# Roberto_shield_sch.net
KiCad netlist of a schematic drawn in Altium Designer
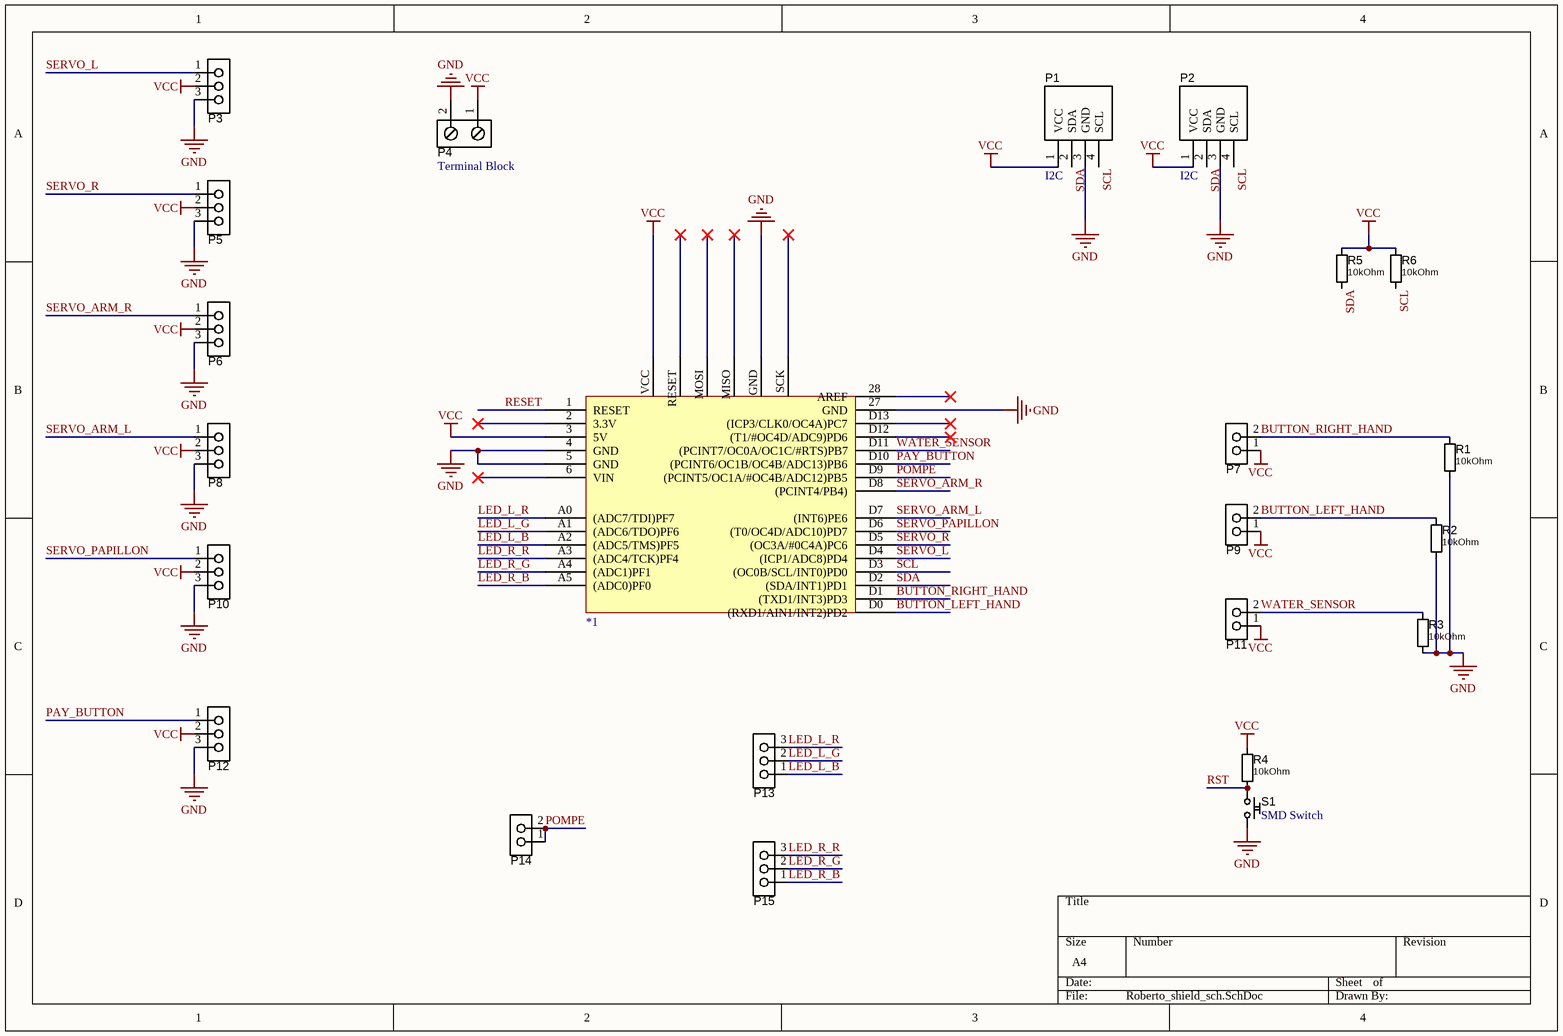
[diagram p0: Roberto_shield_sch.SchDoc]

(export (version "E")
  (design (tool "Eeschema 10.0.6"))
  (components
    (comp (ref "*1")
      (value "Leonardo pins with ISP")
      (footprint "Leonardo pins with ISP")
      (libsource (lib "patricklib") (part "Leonardo pins with ISP"))
    )
    (comp (ref "P1")
      (value "I2C")
      (footprint "TYCO/215079-4")
      (description "Micromatch I2C Connector")
      (libsource (lib "andylib") (part "Micromatch-I2C"))
    )
    (comp (ref "P2")
      (value "I2C")
      (footprint "TYCO/215079-4")
      (description "Micromatch I2C Connector")
      (libsource (lib "andylib") (part "Micromatch-I2C"))
    )
    (comp (ref "P3")
      (value "Header 3")
      (footprint "HEADER1x3")
      (description "Header, 3-Pin")
      (fields (field (name "PUBLISHER") "Altium Limited"))
      (libsource (lib "") (part "Header 3_1"))
    )
    (comp (ref "P4")
      (value "Terminal Block")
      (footprint "Phoenix PT 2-Pole")
      (description "2-Pin Screw Terminal")
      (fields (field (name "PUBLISHER") "Altium Limited"))
      (libsource (lib "andylib") (part "Screw Block 2"))
    )
    (comp (ref "P5")
      (value "Header 3")
      (footprint "HEADER1x3")
      (description "Header, 3-Pin")
      (fields (field (name "PUBLISHER") "Altium Limited"))
      (libsource (lib "") (part "Header 3_1"))
    )
    (comp (ref "P6")
      (value "Header 3")
      (footprint "HEADER1x3")
      (description "Header, 3-Pin")
      (fields (field (name "PUBLISHER") "Altium Limited"))
      (libsource (lib "") (part "Header 3_1"))
    )
    (comp (ref "P7")
      (value "Header 2")
      (footprint "HEADER1x2")
      (description "Header, 2-Pin")
      (fields (field (name "PUBLISHER") "Altium Limited"))
      (libsource (lib "andylib") (part "Header 2"))
    )
    (comp (ref "P8")
      (value "Header 3")
      (footprint "HEADER1x3")
      (description "Header, 3-Pin")
      (fields (field (name "PUBLISHER") "Altium Limited"))
      (libsource (lib "") (part "Header 3_1"))
    )
    (comp (ref "P9")
      (value "Header 2")
      (footprint "HEADER1x2")
      (description "Header, 2-Pin")
      (fields (field (name "PUBLISHER") "Altium Limited"))
      (libsource (lib "andylib") (part "Header 2"))
    )
    (comp (ref "P10")
      (value "Header 3")
      (footprint "HEADER1x3")
      (description "Header, 3-Pin")
      (fields (field (name "PUBLISHER") "Altium Limited"))
      (libsource (lib "") (part "Header 3_1"))
    )
    (comp (ref "P11")
      (value "Header 2")
      (footprint "HEADER1x2")
      (description "Header, 2-Pin")
      (fields (field (name "PUBLISHER") "Altium Limited"))
      (libsource (lib "andylib") (part "Header 2"))
    )
    (comp (ref "P12")
      (value "Header 3")
      (footprint "HEADER1x3")
      (description "Header, 3-Pin")
      (fields (field (name "PUBLISHER") "Altium Limited"))
      (libsource (lib "") (part "Header 3_1"))
    )
    (comp (ref "P13")
      (value "Header 3")
      (footprint "HEADER1x3")
      (description "Header, 3-Pin")
      (fields (field (name "PUBLISHER") "Altium Limited"))
      (libsource (lib "andylib") (part "Header 3"))
    )
    (comp (ref "P14")
      (value "Header 2")
      (footprint "HEADER1x2")
      (description "Header, 2-Pin")
      (fields (field (name "PUBLISHER") "Altium Limited"))
      (libsource (lib "andylib") (part "Header 2"))
    )
    (comp (ref "P15")
      (value "Header 3")
      (footprint "HEADER1x3")
      (description "Header, 3-Pin")
      (fields (field (name "PUBLISHER") "Altium Limited"))
      (libsource (lib "andylib") (part "Header 3"))
    )
    (comp (ref "R1")
      (value "10kOhm")
      (footprint "R/0805")
      (description "Resistor")
      (fields (field (name "PUBLISHER") "Altium Limited"))
      (libsource (lib "andylib") (part "R"))
    )
    (comp (ref "R2")
      (value "10kOhm")
      (footprint "R/0805")
      (description "Resistor")
      (fields (field (name "PUBLISHER") "Altium Limited"))
      (libsource (lib "andylib") (part "R"))
    )
    (comp (ref "R3")
      (value "10kOhm")
      (footprint "R/0805")
      (description "Resistor")
      (fields (field (name "PUBLISHER") "Altium Limited"))
      (libsource (lib "andylib") (part "R"))
    )
    (comp (ref "R4")
      (value "10kOhm")
      (footprint "R/0805")
      (description "Resistor")
      (fields (field (name "PUBLISHER") "Altium Limited"))
      (libsource (lib "andylib") (part "R"))
    )
    (comp (ref "R5")
      (value "10kOhm")
      (footprint "R/0805")
      (description "Resistor")
      (fields (field (name "PUBLISHER") "Altium Limited"))
      (libsource (lib "andylib") (part "R"))
    )
    (comp (ref "R6")
      (value "10kOhm")
      (footprint "R/0805")
      (description "Resistor")
      (fields (field (name "PUBLISHER") "Altium Limited"))
      (libsource (lib "andylib") (part "R"))
    )
    (comp (ref "S1")
      (value "SMD Switch")
      (footprint "SMD_SW_Red")
      (description "Switch")
      (fields (field (name "PUBLISHER") "Altium Limited"))
      (libsource (lib "andylib") (part "SMD Switch"))
    )
  )
  (nets
    (net (code "1") (name "/BUTTON_LEFT_HAND") (class "Default")
      (node (ref "*1") (pin "D0") (pinfunction "(RXD1/AIN1/INT2)PD2_D0") (pintype "passive"))
      (node (ref "P9") (pin "2") (pinfunction "2_2") (pintype "passive"))
      (node (ref "R2") (pin "2") (pinfunction "2_2") (pintype "passive"))
    )
    (net (code "2") (name "/BUTTON_RIGHT_HAND") (class "Default")
      (node (ref "*1") (pin "D1") (pinfunction "(TXD1/INT3)PD3_D1") (pintype "passive"))
      (node (ref "P7") (pin "2") (pinfunction "2_2") (pintype "passive"))
      (node (ref "R1") (pin "2") (pinfunction "2_2") (pintype "passive"))
    )
    (net (code "3") (name "/LED_L_B") (class "Default")
      (node (ref "*1") (pin "A2") (pinfunction "(ADC5/TMS)PF5_A2") (pintype "passive"))
      (node (ref "P13") (pin "1") (pinfunction "1_1") (pintype "passive"))
    )
    (net (code "4") (name "/LED_L_G") (class "Default")
      (node (ref "*1") (pin "A1") (pinfunction "(ADC6/TDO)PF6_A1") (pintype "passive"))
      (node (ref "P13") (pin "2") (pinfunction "2_2") (pintype "passive"))
    )
    (net (code "5") (name "/LED_L_R") (class "Default")
      (node (ref "*1") (pin "A0") (pinfunction "(ADC7/TDI)PF7_A0") (pintype "passive"))
      (node (ref "P13") (pin "3") (pinfunction "3_3") (pintype "passive"))
    )
    (net (code "6") (name "/LED_R_B") (class "Default")
      (node (ref "*1") (pin "A5") (pinfunction "(ADC0)PF0_A5") (pintype "passive"))
      (node (ref "P15") (pin "1") (pinfunction "1_1") (pintype "passive"))
    )
    (net (code "7") (name "/LED_R_G") (class "Default")
      (node (ref "*1") (pin "A4") (pinfunction "(ADC1)PF1_A4") (pintype "passive"))
      (node (ref "P15") (pin "2") (pinfunction "2_2") (pintype "passive"))
    )
    (net (code "8") (name "/LED_R_R") (class "Default")
      (node (ref "*1") (pin "A3") (pinfunction "(ADC4/TCK)PF4_A3") (pintype "passive"))
      (node (ref "P15") (pin "3") (pinfunction "3_3") (pintype "passive"))
    )
    (net (code "9") (name "/PAY_BUTTON") (class "Default")
      (node (ref "*1") (pin "D10") (pinfunction "(PCINT6/OC1B/OC4B/ADC13)PB6_D10") (pintype "passive"))
      (node (ref "P12") (pin "1") (pinfunction "1_1") (pintype "passive"))
    )
    (net (code "10") (name "/POMPE") (class "Default")
      (node (ref "*1") (pin "D9") (pinfunction "(PCINT5/OC1A/#OC4B/ADC12)PB5_D9") (pintype "passive"))
      (node (ref "P14") (pin "1") (pinfunction "1_1") (pintype "passive"))
      (node (ref "P14") (pin "2") (pinfunction "2_2") (pintype "passive"))
    )
    (net (code "11") (name "/RESET") (class "Default")
      (node (ref "*1") (pin "1") (pinfunction "RESET_1") (pintype "passive"))
    )
    (net (code "12") (name "/RST") (class "Default")
      (node (ref "R4") (pin "1") (pinfunction "1_1") (pintype "passive"))
      (node (ref "S1") (pin "1") (pinfunction "1_1") (pintype "passive"))
    )
    (net (code "13") (name "/SCL") (class "Default")
      (node (ref "*1") (pin "D3") (pinfunction "(OC0B/SCL/INT0)PD0_D3") (pintype "passive"))
      (node (ref "P1") (pin "4") (pinfunction "SCL_4") (pintype "passive"))
      (node (ref "P2") (pin "4") (pinfunction "SCL_4") (pintype "passive"))
      (node (ref "R6") (pin "1") (pinfunction "1_1") (pintype "passive"))
    )
    (net (code "14") (name "/SDA") (class "Default")
      (node (ref "*1") (pin "D2") (pinfunction "(SDA/INT1)PD1_D2") (pintype "passive"))
      (node (ref "P1") (pin "2") (pinfunction "SDA_2") (pintype "passive"))
      (node (ref "P2") (pin "2") (pinfunction "SDA_2") (pintype "passive"))
      (node (ref "R5") (pin "1") (pinfunction "1_1") (pintype "passive"))
    )
    (net (code "15") (name "/SERVO_ARM_L") (class "Default")
      (node (ref "*1") (pin "D7") (pinfunction "(INT6)PE6_D7") (pintype "passive"))
      (node (ref "P8") (pin "1") (pinfunction "1_1") (pintype "passive"))
    )
    (net (code "16") (name "/SERVO_ARM_R") (class "Default")
      (node (ref "*1") (pin "D8") (pinfunction "(PCINT4/PB4)_D8") (pintype "passive"))
      (node (ref "P6") (pin "1") (pinfunction "1_1") (pintype "passive"))
    )
    (net (code "17") (name "/SERVO_L") (class "Default")
      (node (ref "*1") (pin "D4") (pinfunction "(ICP1/ADC8)PD4_D4") (pintype "passive"))
      (node (ref "P3") (pin "1") (pinfunction "1_1") (pintype "passive"))
    )
    (net (code "18") (name "/SERVO_PAPILLON") (class "Default")
      (node (ref "*1") (pin "D6") (pinfunction "(T0/OC4D/ADC10)PD7_D6") (pintype "passive"))
      (node (ref "P10") (pin "1") (pinfunction "1_1") (pintype "passive"))
    )
    (net (code "19") (name "/SERVO_R") (class "Default")
      (node (ref "*1") (pin "D5") (pinfunction "(OC3A/#0C4A)PC6_D5") (pintype "passive"))
      (node (ref "P5") (pin "1") (pinfunction "1_1") (pintype "passive"))
    )
    (net (code "20") (name "/WATER_SENSOR") (class "Default")
      (node (ref "*1") (pin "D11") (pinfunction "(PCINT7/OC0A/OC1C/#RTS)PB7_D11") (pintype "passive"))
      (node (ref "P11") (pin "2") (pinfunction "2_2") (pintype "passive"))
      (node (ref "R3") (pin "2") (pinfunction "2_2") (pintype "passive"))
    )
    (net (code "21") (name "GND") (class "Default")
      (node (ref "*1") (pin "27") (pinfunction "GND_27") (pintype "passive"))
      (node (ref "*1") (pin "4") (pinfunction "GND_4") (pintype "passive"))
      (node (ref "*1") (pin "5") (pinfunction "GND_5") (pintype "passive"))
      (node (ref "P1") (pin "3") (pinfunction "GND_3") (pintype "passive"))
      (node (ref "P10") (pin "3") (pinfunction "3_3") (pintype "passive"))
      (node (ref "P12") (pin "3") (pinfunction "3_3") (pintype "passive"))
      (node (ref "P2") (pin "3") (pinfunction "GND_3") (pintype "passive"))
      (node (ref "P3") (pin "3") (pinfunction "3_3") (pintype "passive"))
      (node (ref "P4") (pin "2") (pinfunction "2_2") (pintype "passive"))
      (node (ref "P5") (pin "3") (pinfunction "3_3") (pintype "passive"))
      (node (ref "P6") (pin "3") (pinfunction "3_3") (pintype "passive"))
      (node (ref "P8") (pin "3") (pinfunction "3_3") (pintype "passive"))
      (node (ref "R1") (pin "1") (pinfunction "1_1") (pintype "passive"))
      (node (ref "R2") (pin "1") (pinfunction "1_1") (pintype "passive"))
      (node (ref "R3") (pin "1") (pinfunction "1_1") (pintype "passive"))
      (node (ref "S1") (pin "2") (pinfunction "2_2") (pintype "passive"))
    )
    (net (code "22") (name "VCC") (class "Default")
      (node (ref "*1") (pin "3") (pinfunction "5V_3") (pintype "passive"))
      (node (ref "P1") (pin "1") (pinfunction "VCC_1") (pintype "passive"))
      (node (ref "P10") (pin "2") (pinfunction "2_2") (pintype "passive"))
      (node (ref "P11") (pin "1") (pinfunction "1_1") (pintype "passive"))
      (node (ref "P12") (pin "2") (pinfunction "2_2") (pintype "passive"))
      (node (ref "P2") (pin "1") (pinfunction "VCC_1") (pintype "passive"))
      (node (ref "P3") (pin "2") (pinfunction "2_2") (pintype "passive"))
      (node (ref "P4") (pin "1") (pinfunction "1_1") (pintype "passive"))
      (node (ref "P5") (pin "2") (pinfunction "2_2") (pintype "passive"))
      (node (ref "P6") (pin "2") (pinfunction "2_2") (pintype "passive"))
      (node (ref "P7") (pin "1") (pinfunction "1_1") (pintype "passive"))
      (node (ref "P8") (pin "2") (pinfunction "2_2") (pintype "passive"))
      (node (ref "P9") (pin "1") (pinfunction "1_1") (pintype "passive"))
      (node (ref "R4") (pin "2") (pinfunction "2_2") (pintype "passive"))
      (node (ref "R5") (pin "2") (pinfunction "2_2") (pintype "passive"))
      (node (ref "R6") (pin "2") (pinfunction "2_2") (pintype "passive"))
    )
    (net (code "23") (name "unconnected-(*1-(ICP3{slash}CLK0{slash}OC4A)PC7-PadD13)") (class "Default")
      (node (ref "*1") (pin "D13") (pinfunction "(ICP3/CLK0/OC4A)PC7_D13") (pintype "passive+no_connect"))
    )
    (net (code "24") (name "unconnected-(*1-(T1{slash}#OC4D{slash}ADC9)PD6-PadD12)") (class "Default")
      (node (ref "*1") (pin "D12") (pinfunction "(T1/#OC4D/ADC9)PD6_D12") (pintype "passive+no_connect"))
    )
    (net (code "25") (name "unconnected-(*1-3.3V-Pad2)") (class "Default")
      (node (ref "*1") (pin "2") (pinfunction "3.3V_2") (pintype "passive+no_connect"))
    )
    (net (code "26") (name "unconnected-(*1-AREF-Pad28)") (class "Default")
      (node (ref "*1") (pin "28") (pinfunction "AREF_28") (pintype "passive+no_connect"))
    )
    (net (code "27") (name "unconnected-(*1-D14-PadVCC)") (class "Default")
      (node (ref "*1") (pin "VCC") (pinfunction "D14_VCC") (pintype "passive"))
    )
    (net (code "28") (name "unconnected-(*1-D15-PadRESET)") (class "Default")
      (node (ref "*1") (pin "RESET") (pinfunction "D15_RESET") (pintype "passive"))
    )
    (net (code "29") (name "unconnected-(*1-D16-PadMOSI)") (class "Default")
      (node (ref "*1") (pin "MOSI") (pinfunction "D16_MOSI") (pintype "passive"))
    )
    (net (code "30") (name "unconnected-(*1-D17-PadMISO)") (class "Default")
      (node (ref "*1") (pin "MISO") (pinfunction "D17_MISO") (pintype "passive"))
    )
    (net (code "31") (name "unconnected-(*1-D18-PadGND)") (class "Default")
      (node (ref "*1") (pin "GND") (pinfunction "D18_GND") (pintype "passive"))
    )
    (net (code "32") (name "unconnected-(*1-D19-PadSCK)") (class "Default")
      (node (ref "*1") (pin "SCK") (pinfunction "D19_SCK") (pintype "passive"))
    )
    (net (code "33") (name "unconnected-(*1-VIN-Pad6)") (class "Default")
      (node (ref "*1") (pin "6") (pinfunction "VIN_6") (pintype "passive+no_connect"))
    )
  )
)
